# Voltege_inverter.net
KiCad netlist of a schematic drawn in Altium Designer
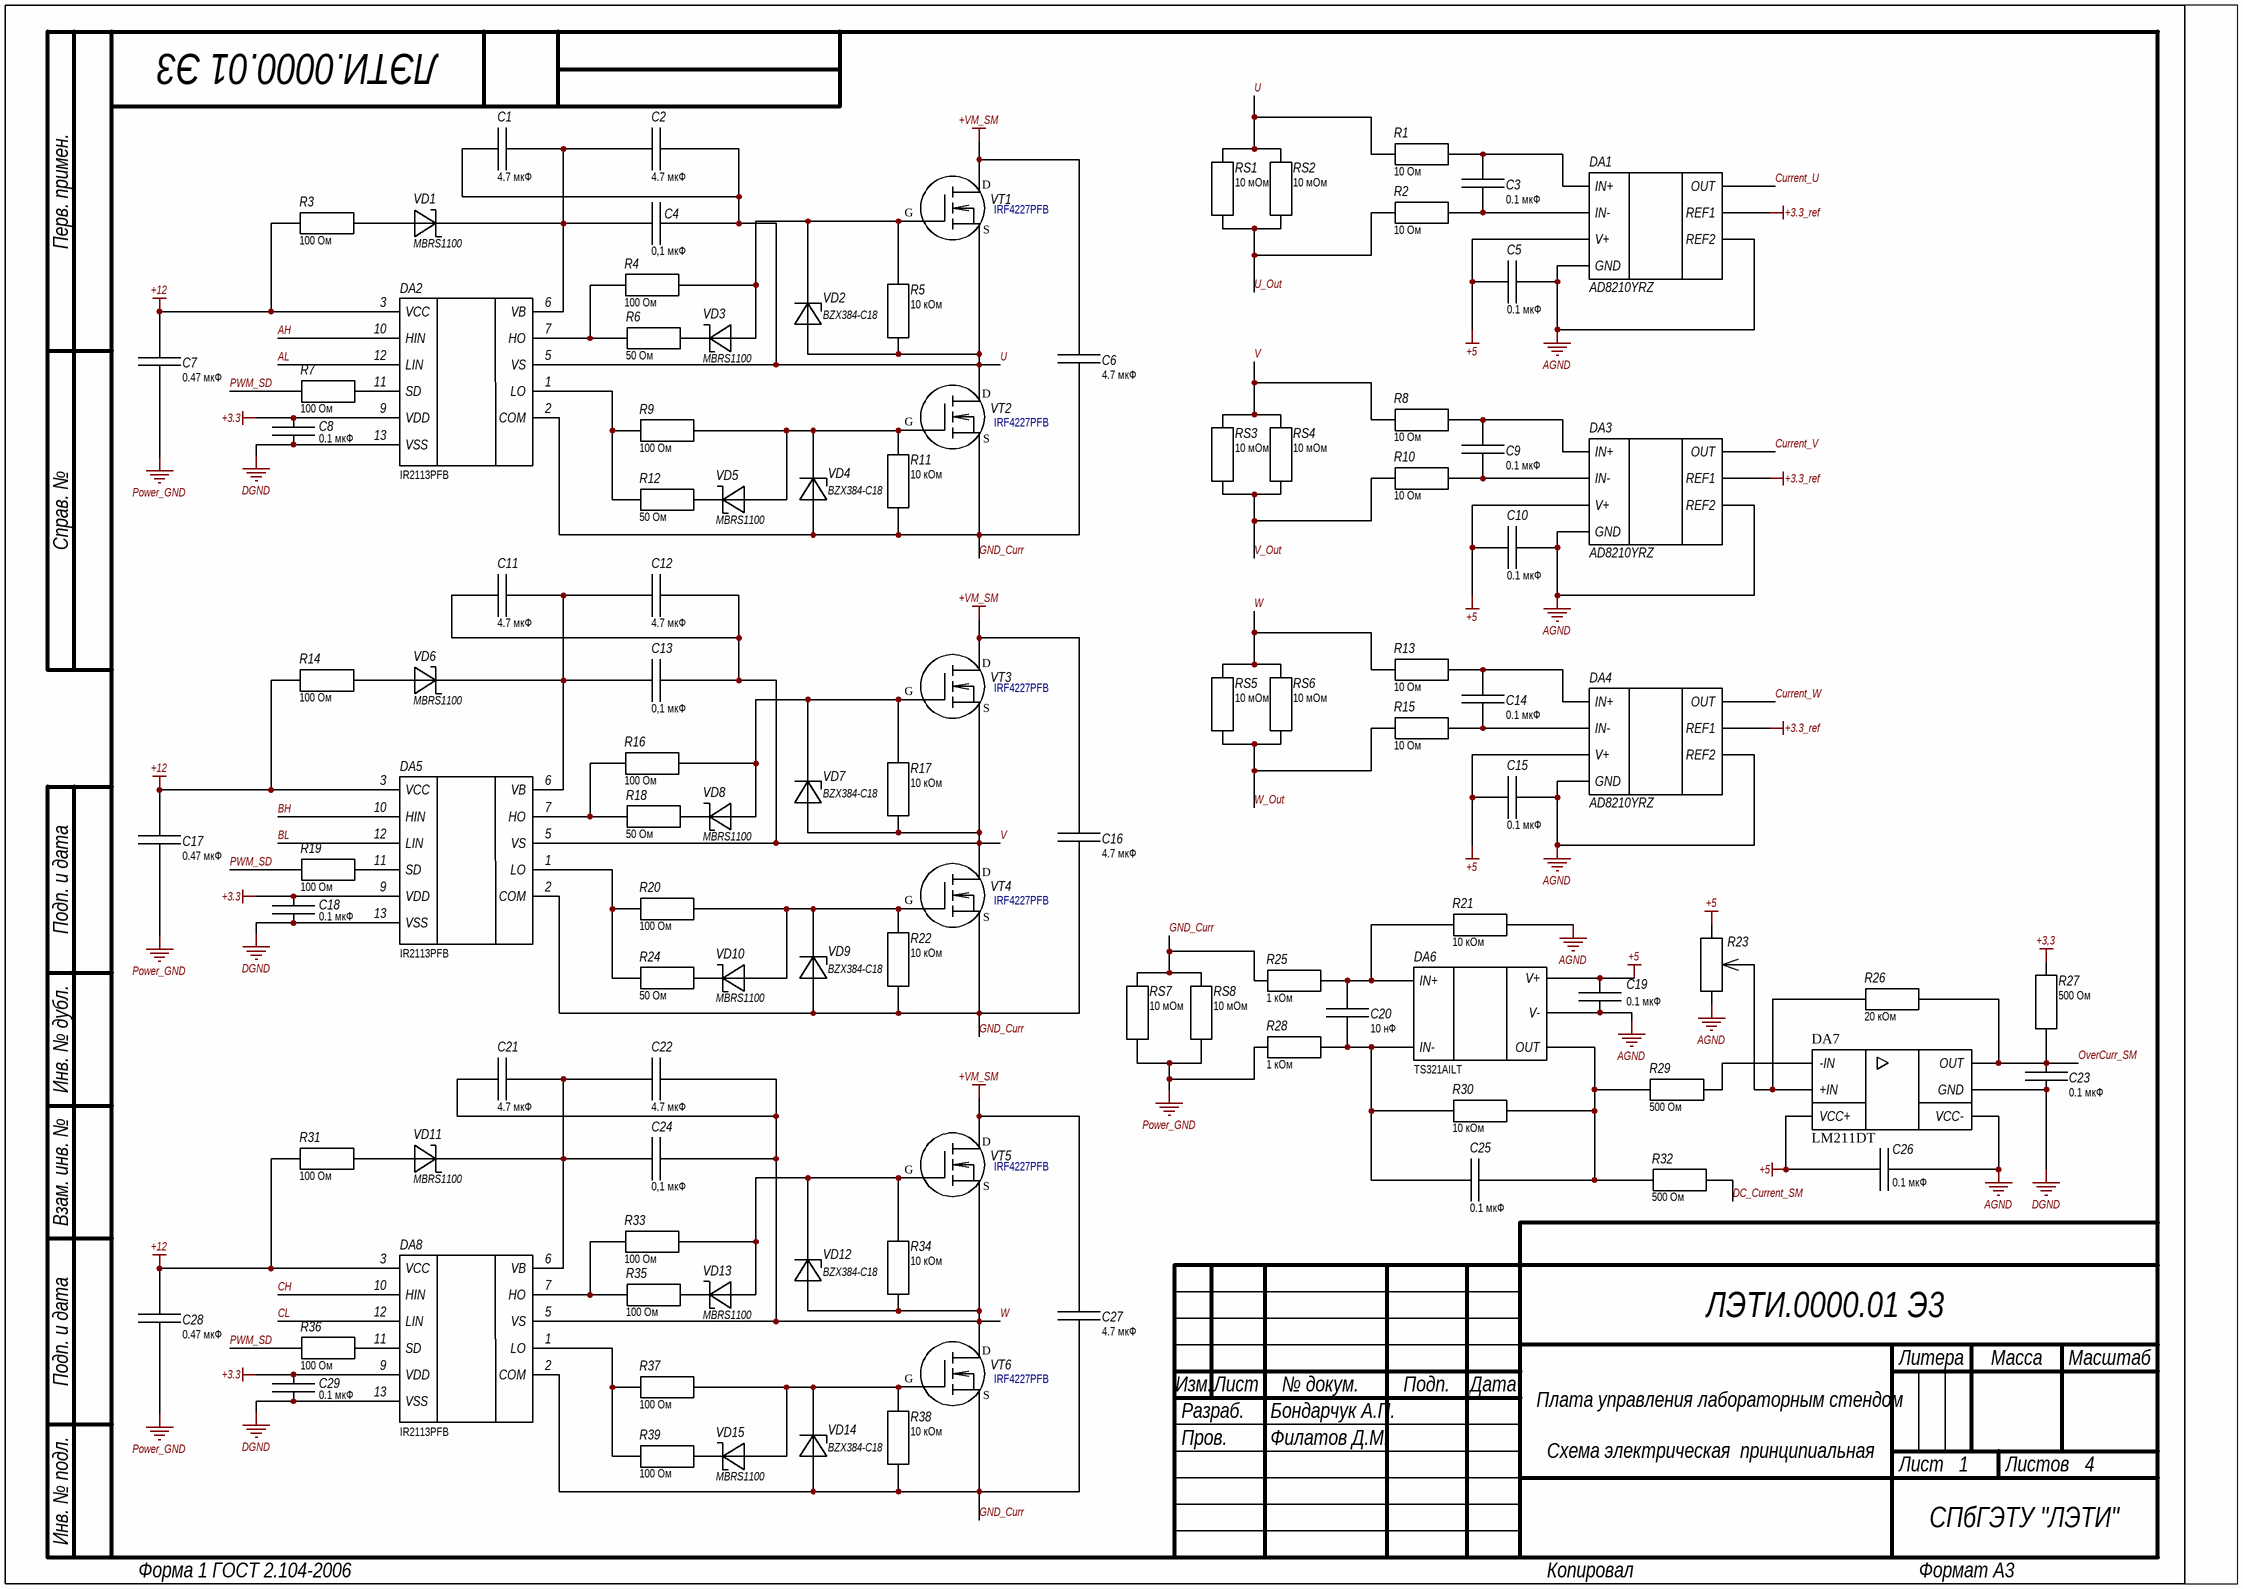
[diagram p0: Voltege_inverter.SchDoc]

(export (version "E")
  (design (tool "Eeschema 10.0.6"))
  (components
    (comp (ref "C1")
      (value "4.7 мкФ")
      (footprint "CC1210")
      (fields (field (name "VOLTAGE") "100В") (field (name "Comment") "Capacitor"))
      (libsource (lib "Main_components") (part "Capacitor"))
    )
    (comp (ref "C2")
      (value "4.7 мкФ")
      (footprint "CC1210")
      (fields (field (name "VOLTAGE") "100В") (field (name "Comment") "Capacitor"))
      (libsource (lib "Main_components") (part "Capacitor"))
    )
    (comp (ref "C3")
      (value "0.1 мкФ")
      (footprint "CC1206")
      (fields (field (name "VOLTAGE") "100В") (field (name "Comment") "Capacitor"))
      (libsource (lib "Main_components") (part "Capacitor"))
    )
    (comp (ref "C4")
      (value "0,1 мкФ")
      (footprint "CC0805")
      (fields (field (name "VOLTAGE") "100В") (field (name "Comment") "Capacitor"))
      (libsource (lib "Main_components") (part "Capacitor"))
    )
    (comp (ref "C5")
      (value "0.1 мкФ")
      (footprint "CC0603")
      (fields (field (name "VOLTAGE") "16В") (field (name "Comment") "Capacitor"))
      (libsource (lib "Main_components") (part "Capacitor"))
    )
    (comp (ref "C6")
      (value "4.7 мкФ")
      (footprint "CC1210")
      (fields (field (name "VOLTAGE") "100В") (field (name "Comment") "Capacitor"))
      (libsource (lib "Main_components") (part "Capacitor"))
    )
    (comp (ref "C7")
      (value "0.47 мкФ")
      (footprint "CC1206")
      (fields (field (name "VOLTAGE") "50В") (field (name "Comment") "Capacitor"))
      (libsource (lib "Main_components") (part "Capacitor"))
    )
    (comp (ref "C8")
      (value "0.1 мкФ")
      (footprint "CC0603")
      (fields (field (name "VOLTAGE") "16В") (field (name "Comment") "Capacitor"))
      (libsource (lib "Main_components") (part "Capacitor"))
    )
    (comp (ref "C9")
      (value "0.1 мкФ")
      (footprint "CC1206")
      (fields (field (name "VOLTAGE") "100В") (field (name "Comment") "Capacitor"))
      (libsource (lib "Main_components") (part "Capacitor"))
    )
    (comp (ref "C10")
      (value "0.1 мкФ")
      (footprint "CC0603")
      (fields (field (name "VOLTAGE") "16В") (field (name "Comment") "Capacitor"))
      (libsource (lib "Main_components") (part "Capacitor"))
    )
    (comp (ref "C11")
      (value "4.7 мкФ")
      (footprint "CC1210")
      (fields (field (name "VOLTAGE") "100В") (field (name "Comment") "Capacitor"))
      (libsource (lib "Main_components") (part "Capacitor"))
    )
    (comp (ref "C12")
      (value "4.7 мкФ")
      (footprint "CC1210")
      (fields (field (name "VOLTAGE") "100В") (field (name "Comment") "Capacitor"))
      (libsource (lib "Main_components") (part "Capacitor"))
    )
    (comp (ref "C13")
      (value "0,1 мкФ")
      (footprint "CC0805")
      (fields (field (name "VOLTAGE") "100В") (field (name "Comment") "Capacitor"))
      (libsource (lib "Main_components") (part "Capacitor"))
    )
    (comp (ref "C14")
      (value "0.1 мкФ")
      (footprint "CC1206")
      (fields (field (name "VOLTAGE") "100В") (field (name "Comment") "Capacitor"))
      (libsource (lib "Main_components") (part "Capacitor"))
    )
    (comp (ref "C15")
      (value "0.1 мкФ")
      (footprint "CC0603")
      (fields (field (name "VOLTAGE") "16В") (field (name "Comment") "Capacitor"))
      (libsource (lib "Main_components") (part "Capacitor"))
    )
    (comp (ref "C16")
      (value "4.7 мкФ")
      (footprint "CC1210")
      (fields (field (name "VOLTAGE") "100В") (field (name "Comment") "Capacitor"))
      (libsource (lib "Main_components") (part "Capacitor"))
    )
    (comp (ref "C17")
      (value "0.47 мкФ")
      (footprint "CC1206")
      (fields (field (name "VOLTAGE") "50В") (field (name "Comment") "Capacitor"))
      (libsource (lib "Main_components") (part "Capacitor"))
    )
    (comp (ref "C18")
      (value "0.1 мкФ")
      (footprint "CC0603")
      (fields (field (name "VOLTAGE") "16В") (field (name "Comment") "Capacitor"))
      (libsource (lib "Main_components") (part "Capacitor"))
    )
    (comp (ref "C19")
      (value "0.1 мкФ")
      (footprint "CC0603")
      (fields (field (name "VOLTAGE") "16В") (field (name "Comment") "Capacitor"))
      (libsource (lib "Main_components") (part "Capacitor"))
    )
    (comp (ref "C20")
      (value "10 нФ")
      (footprint "CC0805")
      (fields (field (name "VOLTAGE") "50В") (field (name "Comment") "Capacitor"))
      (libsource (lib "Main_components") (part "Capacitor"))
    )
    (comp (ref "C21")
      (value "4.7 мкФ")
      (footprint "CC1210")
      (fields (field (name "VOLTAGE") "100В") (field (name "Comment") "Capacitor"))
      (libsource (lib "Main_components") (part "Capacitor"))
    )
    (comp (ref "C22")
      (value "4.7 мкФ")
      (footprint "CC1210")
      (fields (field (name "VOLTAGE") "100В") (field (name "Comment") "Capacitor"))
      (libsource (lib "Main_components") (part "Capacitor"))
    )
    (comp (ref "C23")
      (value "0.1 мкФ")
      (footprint "CC0603")
      (fields (field (name "VOLTAGE") "16В") (field (name "Comment") "Capacitor"))
      (libsource (lib "Main_components") (part "Capacitor"))
    )
    (comp (ref "C24")
      (value "0,1 мкФ")
      (footprint "CC0805")
      (fields (field (name "VOLTAGE") "100В") (field (name "Comment") "Capacitor"))
      (libsource (lib "Main_components") (part "Capacitor"))
    )
    (comp (ref "C25")
      (value "0.1 мкФ")
      (footprint "CC1206")
      (fields (field (name "VOLTAGE") "100В") (field (name "Comment") "Capacitor"))
      (libsource (lib "Main_components") (part "Capacitor"))
    )
    (comp (ref "C26")
      (value "0.1 мкФ")
      (footprint "CC0603")
      (fields (field (name "VOLTAGE") "16В") (field (name "Comment") "Capacitor"))
      (libsource (lib "Main_components") (part "Capacitor"))
    )
    (comp (ref "C27")
      (value "4.7 мкФ")
      (footprint "CC1210")
      (fields (field (name "VOLTAGE") "100В") (field (name "Comment") "Capacitor"))
      (libsource (lib "Main_components") (part "Capacitor"))
    )
    (comp (ref "C28")
      (value "0.47 мкФ")
      (footprint "CC1206")
      (fields (field (name "VOLTAGE") "50В") (field (name "Comment") "Capacitor"))
      (libsource (lib "Main_components") (part "Capacitor"))
    )
    (comp (ref "C29")
      (value "0.1 мкФ")
      (footprint "CC0603")
      (fields (field (name "VOLTAGE") "16В") (field (name "Comment") "Capacitor"))
      (libsource (lib "Main_components") (part "Capacitor"))
    )
    (comp (ref "DA1") (value "AD8210YRZ") (footprint "SO8") (libsource (lib "Microcircuits") (part "AD8210")))
    (comp (ref "DA2")
      (value "IR2113PFB")
      (footprint "DIP14")
      (libsource (lib "Microcircuits") (part "IR2113PFB"))
    )
    (comp (ref "DA3") (value "AD8210YRZ") (footprint "SO8") (libsource (lib "Microcircuits") (part "AD8210")))
    (comp (ref "DA4") (value "AD8210YRZ") (footprint "SO8") (libsource (lib "Microcircuits") (part "AD8210")))
    (comp (ref "DA5")
      (value "IR2113PFB")
      (footprint "DIP14")
      (libsource (lib "Microcircuits") (part "IR2113PFB"))
    )
    (comp (ref "DA6")
      (value "TS321AILT")
      (footprint "SOT-23-5")
      (description "Одиночный операционный усилитель.")
      (libsource (lib "Microcircuits") (part "TS321AILT"))
    )
    (comp (ref "DA7")
      (value "LM211DT")
      (footprint "SO8")
      (description "Компаратор")
      (libsource (lib "Microcircuits") (part "LM211DT"))
    )
    (comp (ref "DA8")
      (value "IR2113PFB")
      (footprint "DIP14")
      (libsource (lib "Microcircuits") (part "IR2113PFB"))
    )
    (comp (ref "R1")
      (value "10 Ом")
      (footprint "RC1206")
      (fields (field (name "POWER") "250 мВт") (field (name "Comment") "Resistor"))
      (libsource (lib "Main_components") (part "Resistor"))
    )
    (comp (ref "R2")
      (value "10 Ом")
      (footprint "RC1206")
      (fields (field (name "POWER") "250 мВт") (field (name "Comment") "Resistor"))
      (libsource (lib "Main_components") (part "Resistor"))
    )
    (comp (ref "R3")
      (value "100 Ом")
      (footprint "RC2512")
      (fields (field (name "POWER") "1 Вт") (field (name "Comment") "Resistor"))
      (libsource (lib "Main_components") (part "Resistor"))
    )
    (comp (ref "R4")
      (value "100 Ом")
      (footprint "RC2512")
      (fields (field (name "POWER") "1 Вт") (field (name "Comment") "Resistor"))
      (libsource (lib "Main_components") (part "Resistor"))
    )
    (comp (ref "R5")
      (value "10 кОм")
      (footprint "RC0805")
      (fields (field (name "POWER") "125 мВт") (field (name "Comment") "Resistor"))
      (libsource (lib "Main_components") (part "Resistor"))
    )
    (comp (ref "R6")
      (value "50 Ом")
      (footprint "RC2512")
      (fields (field (name "POWER") "1 Вт") (field (name "Comment") "Resistor"))
      (libsource (lib "Main_components") (part "Resistor"))
    )
    (comp (ref "R7")
      (value "100 Ом")
      (footprint "RC0603")
      (fields (field (name "POWER") "100 мВт") (field (name "Comment") "Resistor"))
      (libsource (lib "Main_components") (part "Resistor"))
    )
    (comp (ref "R8")
      (value "10 Ом")
      (footprint "RC1206")
      (fields (field (name "POWER") "250 мВт") (field (name "Comment") "Resistor"))
      (libsource (lib "Main_components") (part "Resistor"))
    )
    (comp (ref "R9")
      (value "100 Ом")
      (footprint "RC2512")
      (fields (field (name "POWER") "1 Вт") (field (name "Comment") "Resistor"))
      (libsource (lib "Main_components") (part "Resistor"))
    )
    (comp (ref "R10")
      (value "10 Ом")
      (footprint "RC1206")
      (fields (field (name "POWER") "250 мВт") (field (name "Comment") "Resistor"))
      (libsource (lib "Main_components") (part "Resistor"))
    )
    (comp (ref "R11")
      (value "10 кОм")
      (footprint "RC0805")
      (fields (field (name "POWER") "125 мВт") (field (name "Comment") "Resistor"))
      (libsource (lib "Main_components") (part "Resistor"))
    )
    (comp (ref "R12")
      (value "50 Ом")
      (footprint "RC2512")
      (fields (field (name "POWER") "1 Вт") (field (name "Comment") "Resistor"))
      (libsource (lib "Main_components") (part "Resistor"))
    )
    (comp (ref "R13")
      (value "10 Ом")
      (footprint "RC1206")
      (fields (field (name "POWER") "250 мВт") (field (name "Comment") "Resistor"))
      (libsource (lib "Main_components") (part "Resistor"))
    )
    (comp (ref "R14")
      (value "100 Ом")
      (footprint "RC2512")
      (fields (field (name "POWER") "1 Вт") (field (name "Comment") "Resistor"))
      (libsource (lib "Main_components") (part "Resistor"))
    )
    (comp (ref "R15")
      (value "10 Ом")
      (footprint "RC1206")
      (fields (field (name "POWER") "250 мВт") (field (name "Comment") "Resistor"))
      (libsource (lib "Main_components") (part "Resistor"))
    )
    (comp (ref "R16")
      (value "100 Ом")
      (footprint "RC2512")
      (fields (field (name "POWER") "1 Вт") (field (name "Comment") "Resistor"))
      (libsource (lib "Main_components") (part "Resistor"))
    )
    (comp (ref "R17")
      (value "10 кОм")
      (footprint "RC0805")
      (fields (field (name "POWER") "125 мВт") (field (name "Comment") "Resistor"))
      (libsource (lib "Main_components") (part "Resistor"))
    )
    (comp (ref "R18")
      (value "50 Ом")
      (footprint "RC2512")
      (fields (field (name "POWER") "1 Вт") (field (name "Comment") "Resistor"))
      (libsource (lib "Main_components") (part "Resistor"))
    )
    (comp (ref "R19")
      (value "100 Ом")
      (footprint "RC0603")
      (fields (field (name "POWER") "100 мВт") (field (name "Comment") "Resistor"))
      (libsource (lib "Main_components") (part "Resistor"))
    )
    (comp (ref "R20")
      (value "100 Ом")
      (footprint "RC2512")
      (fields (field (name "POWER") "1 Вт") (field (name "Comment") "Resistor"))
      (libsource (lib "Main_components") (part "Resistor"))
    )
    (comp (ref "R21")
      (value "10 кОм")
      (footprint "RC0805")
      (fields (field (name "POWER") "125 мВт") (field (name "Comment") "Resistor"))
      (libsource (lib "Main_components") (part "Resistor"))
    )
    (comp (ref "R22")
      (value "10 кОм")
      (footprint "RC0805")
      (fields (field (name "POWER") "125 мВт") (field (name "Comment") "Resistor"))
      (libsource (lib "Main_components") (part "Resistor"))
    )
    (comp (ref "R23") (value "pot") (footprint "3296W") (libsource (lib "Main_components") (part "pot")))
    (comp (ref "R24")
      (value "50 Ом")
      (footprint "RC2512")
      (fields (field (name "POWER") "1 Вт") (field (name "Comment") "Resistor"))
      (libsource (lib "Main_components") (part "Resistor"))
    )
    (comp (ref "R25")
      (value "1 кОм")
      (footprint "RC0805")
      (fields (field (name "POWER") "125 мВт") (field (name "Comment") "Resistor"))
      (libsource (lib "Main_components") (part "Resistor"))
    )
    (comp (ref "R26")
      (value "20 кОм")
      (footprint "RC0805")
      (fields (field (name "POWER") "125 мВт") (field (name "Comment") "Resistor"))
      (libsource (lib "Main_components") (part "Resistor"))
    )
    (comp (ref "R27")
      (value "500 Ом")
      (footprint "RC0805")
      (fields (field (name "POWER") "125 мВт") (field (name "Comment") "Resistor"))
      (libsource (lib "Main_components") (part "Resistor"))
    )
    (comp (ref "R28")
      (value "1 кОм")
      (footprint "RC0805")
      (fields (field (name "POWER") "125 мВт") (field (name "Comment") "Resistor"))
      (libsource (lib "Main_components") (part "Resistor"))
    )
    (comp (ref "R29")
      (value "500 Ом")
      (footprint "RC0805")
      (fields (field (name "POWER") "125 мВт") (field (name "Comment") "Resistor"))
      (libsource (lib "Main_components") (part "Resistor"))
    )
    (comp (ref "R30")
      (value "10 кОм")
      (footprint "RC0805")
      (fields (field (name "POWER") "125 мВт") (field (name "Comment") "Resistor"))
      (libsource (lib "Main_components") (part "Resistor"))
    )
    (comp (ref "R31")
      (value "100 Ом")
      (footprint "RC2512")
      (fields (field (name "POWER") "1 Вт") (field (name "Comment") "Resistor"))
      (libsource (lib "Main_components") (part "Resistor"))
    )
    (comp (ref "R32")
      (value "500 Ом")
      (footprint "RC0805")
      (fields (field (name "POWER") "125 мВт") (field (name "Comment") "Resistor"))
      (libsource (lib "Main_components") (part "Resistor"))
    )
    (comp (ref "R33")
      (value "100 Ом")
      (footprint "RC2512")
      (fields (field (name "POWER") "1 Вт") (field (name "Comment") "Resistor"))
      (libsource (lib "Main_components") (part "Resistor"))
    )
    (comp (ref "R34")
      (value "10 кОм")
      (footprint "RC0805")
      (fields (field (name "POWER") "125 мВт") (field (name "Comment") "Resistor"))
      (libsource (lib "Main_components") (part "Resistor"))
    )
    (comp (ref "R35")
      (value "100 Ом")
      (footprint "RC2512")
      (fields (field (name "POWER") "1 Вт") (field (name "Comment") "Resistor"))
      (libsource (lib "Main_components") (part "Resistor"))
    )
    (comp (ref "R36")
      (value "100 Ом")
      (footprint "RC0603")
      (fields (field (name "POWER") "100 мВт") (field (name "Comment") "Resistor"))
      (libsource (lib "Main_components") (part "Resistor"))
    )
    (comp (ref "R37")
      (value "100 Ом")
      (footprint "RC2512")
      (fields (field (name "POWER") "1 Вт") (field (name "Comment") "Resistor"))
      (libsource (lib "Main_components") (part "Resistor"))
    )
    (comp (ref "R38")
      (value "10 кОм")
      (footprint "RC0805")
      (fields (field (name "POWER") "125 мВт") (field (name "Comment") "Resistor"))
      (libsource (lib "Main_components") (part "Resistor"))
    )
    (comp (ref "R39")
      (value "100 Ом")
      (footprint "RC2512")
      (fields (field (name "POWER") "1 Вт") (field (name "Comment") "Resistor"))
      (libsource (lib "Main_components") (part "Resistor"))
    )
    (comp (ref "RS1")
      (value "10 мОм")
      (footprint "RC2816")
      (fields (field (name "POWER") "2 Вт") (field (name "Comment") "Resistor"))
      (libsource (lib "Main_components") (part "Resistor"))
    )
    (comp (ref "RS2")
      (value "10 мОм")
      (footprint "RC2816")
      (fields (field (name "POWER") "2 Вт") (field (name "Comment") "Resistor"))
      (libsource (lib "Main_components") (part "Resistor"))
    )
    (comp (ref "RS3")
      (value "10 мОм")
      (footprint "RC2816")
      (fields (field (name "POWER") "2 Вт") (field (name "Comment") "Resistor"))
      (libsource (lib "Main_components") (part "Resistor"))
    )
    (comp (ref "RS4")
      (value "10 мОм")
      (footprint "RC2816")
      (fields (field (name "POWER") "2 Вт") (field (name "Comment") "Resistor"))
      (libsource (lib "Main_components") (part "Resistor"))
    )
    (comp (ref "RS5")
      (value "10 мОм")
      (footprint "RC2816")
      (fields (field (name "POWER") "2 Вт") (field (name "Comment") "Resistor"))
      (libsource (lib "Main_components") (part "Resistor"))
    )
    (comp (ref "RS6")
      (value "10 мОм")
      (footprint "RC2816")
      (fields (field (name "POWER") "2 Вт") (field (name "Comment") "Resistor"))
      (libsource (lib "Main_components") (part "Resistor"))
    )
    (comp (ref "RS7")
      (value "10 мОм")
      (footprint "RC2816")
      (fields (field (name "POWER") "2 Вт") (field (name "Comment") "Resistor"))
      (libsource (lib "Main_components") (part "Resistor"))
    )
    (comp (ref "RS8")
      (value "10 мОм")
      (footprint "RC2816")
      (fields (field (name "POWER") "2 Вт") (field (name "Comment") "Resistor"))
      (libsource (lib "Main_components") (part "Resistor"))
    )
    (comp (ref "VD1")
      (value "MBRS1100")
      (footprint "DO-214AA")
      (libsource (lib "Main_components") (part "Shotki"))
    )
    (comp (ref "VD2")
      (value "BZX384-C18")
      (footprint "SOD323")
      (libsource (lib "InvertorSchLib") (part "Zener diode"))
    )
    (comp (ref "VD3")
      (value "MBRS1100")
      (footprint "DO-214AA")
      (libsource (lib "Main_components") (part "Shotki"))
    )
    (comp (ref "VD4")
      (value "BZX384-C18")
      (footprint "SOD323")
      (libsource (lib "InvertorSchLib") (part "Zener diode"))
    )
    (comp (ref "VD5")
      (value "MBRS1100")
      (footprint "DO-214AA")
      (libsource (lib "Main_components") (part "Shotki"))
    )
    (comp (ref "VD6")
      (value "MBRS1100")
      (footprint "DO-214AA")
      (libsource (lib "Main_components") (part "Shotki"))
    )
    (comp (ref "VD7")
      (value "BZX384-C18")
      (footprint "SOD323")
      (libsource (lib "InvertorSchLib") (part "Zener diode"))
    )
    (comp (ref "VD8")
      (value "MBRS1100")
      (footprint "DO-214AA")
      (libsource (lib "Main_components") (part "Shotki"))
    )
    (comp (ref "VD9")
      (value "BZX384-C18")
      (footprint "SOD323")
      (libsource (lib "InvertorSchLib") (part "Zener diode"))
    )
    (comp (ref "VD10")
      (value "MBRS1100")
      (footprint "DO-214AA")
      (libsource (lib "Main_components") (part "Shotki"))
    )
    (comp (ref "VD11")
      (value "MBRS1100")
      (footprint "DO-214AA")
      (libsource (lib "Main_components") (part "Shotki"))
    )
    (comp (ref "VD12")
      (value "BZX384-C18")
      (footprint "SOD323")
      (libsource (lib "InvertorSchLib") (part "Zener diode"))
    )
    (comp (ref "VD13")
      (value "MBRS1100")
      (footprint "DO-214AA")
      (libsource (lib "Main_components") (part "Shotki"))
    )
    (comp (ref "VD14")
      (value "BZX384-C18")
      (footprint "SOD323")
      (libsource (lib "InvertorSchLib") (part "Zener diode"))
    )
    (comp (ref "VD15")
      (value "MBRS1100")
      (footprint "DO-214AA")
      (libsource (lib "Main_components") (part "Shotki"))
    )
    (comp (ref "VT1")
      (value "IRF4227PFB")
      (footprint "TO247-1")
      (libsource (lib "Main_components") (part "N-MOSFET"))
    )
    (comp (ref "VT2")
      (value "IRF4227PFB")
      (footprint "TO247-1")
      (libsource (lib "Main_components") (part "N-MOSFET"))
    )
    (comp (ref "VT3")
      (value "IRF4227PFB")
      (footprint "TO247-1")
      (libsource (lib "Main_components") (part "N-MOSFET"))
    )
    (comp (ref "VT4")
      (value "IRF4227PFB")
      (footprint "TO247-1")
      (libsource (lib "Main_components") (part "N-MOSFET"))
    )
    (comp (ref "VT5")
      (value "IRF4227PFB")
      (footprint "TO247-1")
      (libsource (lib "Main_components") (part "N-MOSFET"))
    )
    (comp (ref "VT6")
      (value "IRF4227PFB")
      (footprint "TO247-1")
      (libsource (lib "Main_components") (part "N-MOSFET"))
    )
  )
  (nets
    (net (code "1") (name "+3,3") (class "Default")
      (node (ref "R27") (pin "2") (pinfunction "2_2") (pintype "passive"))
    )
    (net (code "2") (name "+3.3") (class "Default")
      (node (ref "C18") (pin "2") (pinfunction "2_2") (pintype "passive"))
      (node (ref "C29") (pin "2") (pinfunction "2_2") (pintype "passive"))
      (node (ref "C8") (pin "2") (pinfunction "2_2") (pintype "passive"))
      (node (ref "DA2") (pin "9") (pinfunction "VDD_9") (pintype "passive"))
      (node (ref "DA5") (pin "9") (pinfunction "VDD_9") (pintype "passive"))
      (node (ref "DA8") (pin "9") (pinfunction "VDD_9") (pintype "passive"))
    )
    (net (code "3") (name "+3.3_ref") (class "Default")
      (node (ref "DA1") (pin "7") (pinfunction "REF1_7") (pintype "passive"))
      (node (ref "DA3") (pin "7") (pinfunction "REF1_7") (pintype "passive"))
      (node (ref "DA4") (pin "7") (pinfunction "REF1_7") (pintype "passive"))
    )
    (net (code "4") (name "+5") (class "Default")
      (node (ref "C10") (pin "2") (pinfunction "2_2") (pintype "passive"))
      (node (ref "C15") (pin "2") (pinfunction "2_2") (pintype "passive"))
      (node (ref "C19") (pin "1") (pinfunction "1_1") (pintype "passive"))
      (node (ref "C26") (pin "1") (pinfunction "1_1") (pintype "passive"))
      (node (ref "C5") (pin "2") (pinfunction "2_2") (pintype "passive"))
      (node (ref "DA1") (pin "6") (pinfunction "V+_6") (pintype "passive"))
      (node (ref "DA3") (pin "6") (pinfunction "V+_6") (pintype "passive"))
      (node (ref "DA4") (pin "6") (pinfunction "V+_6") (pintype "passive"))
      (node (ref "DA6") (pin "5") (pinfunction "V+_5") (pintype "passive"))
      (node (ref "DA7") (pin "8") (pinfunction "VCC+_8") (pintype "passive"))
      (node (ref "R23") (pin "1") (pinfunction "1_1") (pintype "passive"))
    )
    (net (code "5") (name "+12") (class "Default")
      (node (ref "C17") (pin "2") (pinfunction "2_2") (pintype "passive"))
      (node (ref "C28") (pin "2") (pinfunction "2_2") (pintype "passive"))
      (node (ref "C7") (pin "2") (pinfunction "2_2") (pintype "passive"))
      (node (ref "DA2") (pin "3") (pinfunction "VCC_3") (pintype "passive"))
      (node (ref "DA5") (pin "3") (pinfunction "VCC_3") (pintype "passive"))
      (node (ref "DA8") (pin "3") (pinfunction "VCC_3") (pintype "passive"))
      (node (ref "R14") (pin "2") (pinfunction "2_2") (pintype "passive"))
      (node (ref "R3") (pin "2") (pinfunction "2_2") (pintype "passive"))
      (node (ref "R31") (pin "2") (pinfunction "2_2") (pintype "passive"))
    )
    (net (code "6") (name "+VM_SM") (class "Default")
      (node (ref "C16") (pin "2") (pinfunction "2_2") (pintype "passive"))
      (node (ref "C27") (pin "2") (pinfunction "2_2") (pintype "passive"))
      (node (ref "C6") (pin "2") (pinfunction "2_2") (pintype "passive"))
      (node (ref "VT1") (pin "D") (pinfunction "D_D") (pintype "passive"))
      (node (ref "VT3") (pin "D") (pinfunction "D_D") (pintype "passive"))
      (node (ref "VT5") (pin "D") (pinfunction "D_D") (pintype "passive"))
    )
    (net (code "7") (name "/AH") (class "Default")
      (node (ref "DA2") (pin "10") (pinfunction "HIN_10") (pintype "passive"))
    )
    (net (code "8") (name "/AL") (class "Default")
      (node (ref "DA2") (pin "12") (pinfunction "LIN_12") (pintype "passive"))
    )
    (net (code "9") (name "/BH") (class "Default")
      (node (ref "DA5") (pin "10") (pinfunction "HIN_10") (pintype "passive"))
    )
    (net (code "10") (name "/BL") (class "Default")
      (node (ref "DA5") (pin "12") (pinfunction "LIN_12") (pintype "passive"))
    )
    (net (code "11") (name "/CH") (class "Default")
      (node (ref "DA8") (pin "10") (pinfunction "HIN_10") (pintype "passive"))
    )
    (net (code "12") (name "/CL") (class "Default")
      (node (ref "DA8") (pin "12") (pinfunction "LIN_12") (pintype "passive"))
    )
    (net (code "13") (name "/Current_U") (class "Default")
      (node (ref "DA1") (pin "5") (pinfunction "OUT_5") (pintype "passive"))
    )
    (net (code "14") (name "/Current_V") (class "Default")
      (node (ref "DA3") (pin "5") (pinfunction "OUT_5") (pintype "passive"))
    )
    (net (code "15") (name "/Current_W") (class "Default")
      (node (ref "DA4") (pin "5") (pinfunction "OUT_5") (pintype "passive"))
    )
    (net (code "16") (name "/DC_Current_SM") (class "Default")
      (node (ref "R32") (pin "2") (pinfunction "2_2") (pintype "passive"))
    )
    (net (code "17") (name "/GND_Curr") (class "Default")
      (node (ref "C16") (pin "1") (pinfunction "1_1") (pintype "passive"))
      (node (ref "C27") (pin "1") (pinfunction "1_1") (pintype "passive"))
      (node (ref "C6") (pin "1") (pinfunction "1_1") (pintype "passive"))
      (node (ref "DA2") (pin "2") (pinfunction "COM_2") (pintype "passive"))
      (node (ref "DA5") (pin "2") (pinfunction "COM_2") (pintype "passive"))
      (node (ref "DA8") (pin "2") (pinfunction "COM_2") (pintype "passive"))
      (node (ref "R11") (pin "2") (pinfunction "2_2") (pintype "passive"))
      (node (ref "R22") (pin "2") (pinfunction "2_2") (pintype "passive"))
      (node (ref "R25") (pin "1") (pinfunction "1_1") (pintype "passive"))
      (node (ref "R38") (pin "2") (pinfunction "2_2") (pintype "passive"))
      (node (ref "RS7") (pin "1") (pinfunction "1_1") (pintype "passive"))
      (node (ref "RS8") (pin "1") (pinfunction "1_1") (pintype "passive"))
      (node (ref "VD14") (pin "A") (pinfunction "A_A") (pintype "passive"))
      (node (ref "VD4") (pin "A") (pinfunction "A_A") (pintype "passive"))
      (node (ref "VD9") (pin "A") (pinfunction "A_A") (pintype "passive"))
      (node (ref "VT2") (pin "S") (pinfunction "S_S") (pintype "passive"))
      (node (ref "VT4") (pin "S") (pinfunction "S_S") (pintype "passive"))
      (node (ref "VT6") (pin "S") (pinfunction "S_S") (pintype "passive"))
    )
    (net (code "18") (name "/OverCurr_SM") (class "Default")
      (node (ref "C23") (pin "2") (pinfunction "2_2") (pintype "passive"))
      (node (ref "DA7") (pin "7") (pinfunction "OUT_7") (pintype "passive"))
      (node (ref "R26") (pin "2") (pinfunction "2_2") (pintype "passive"))
      (node (ref "R27") (pin "1") (pinfunction "1_1") (pintype "passive"))
    )
    (net (code "19") (name "/PWM_SD") (class "Default")
      (node (ref "R19") (pin "2") (pinfunction "2_2") (pintype "passive"))
      (node (ref "R36") (pin "2") (pinfunction "2_2") (pintype "passive"))
      (node (ref "R7") (pin "2") (pinfunction "2_2") (pintype "passive"))
    )
    (net (code "20") (name "/U") (class "Default")
      (node (ref "C1") (pin "2") (pinfunction "2_2") (pintype "passive"))
      (node (ref "C2") (pin "1") (pinfunction "1_1") (pintype "passive"))
      (node (ref "C4") (pin "1") (pinfunction "1_1") (pintype "passive"))
      (node (ref "DA2") (pin "5") (pinfunction "VS_5") (pintype "passive"))
      (node (ref "R1") (pin "2") (pinfunction "2_2") (pintype "passive"))
      (node (ref "R5") (pin "2") (pinfunction "2_2") (pintype "passive"))
      (node (ref "RS1") (pin "1") (pinfunction "1_1") (pintype "passive"))
      (node (ref "RS2") (pin "1") (pinfunction "1_1") (pintype "passive"))
      (node (ref "VD2") (pin "A") (pinfunction "A_A") (pintype "passive"))
      (node (ref "VT1") (pin "S") (pinfunction "S_S") (pintype "passive"))
      (node (ref "VT2") (pin "D") (pinfunction "D_D") (pintype "passive"))
    )
    (net (code "21") (name "/U_Out") (class "Default")
      (node (ref "R2") (pin "2") (pinfunction "2_2") (pintype "passive"))
      (node (ref "RS1") (pin "2") (pinfunction "2_2") (pintype "passive"))
      (node (ref "RS2") (pin "2") (pinfunction "2_2") (pintype "passive"))
    )
    (net (code "22") (name "/V") (class "Default")
      (node (ref "C11") (pin "2") (pinfunction "2_2") (pintype "passive"))
      (node (ref "C12") (pin "1") (pinfunction "1_1") (pintype "passive"))
      (node (ref "C13") (pin "1") (pinfunction "1_1") (pintype "passive"))
      (node (ref "DA5") (pin "5") (pinfunction "VS_5") (pintype "passive"))
      (node (ref "R17") (pin "2") (pinfunction "2_2") (pintype "passive"))
      (node (ref "R8") (pin "2") (pinfunction "2_2") (pintype "passive"))
      (node (ref "RS3") (pin "1") (pinfunction "1_1") (pintype "passive"))
      (node (ref "RS4") (pin "1") (pinfunction "1_1") (pintype "passive"))
      (node (ref "VD7") (pin "A") (pinfunction "A_A") (pintype "passive"))
      (node (ref "VT3") (pin "S") (pinfunction "S_S") (pintype "passive"))
      (node (ref "VT4") (pin "D") (pinfunction "D_D") (pintype "passive"))
    )
    (net (code "23") (name "/V_Out") (class "Default")
      (node (ref "R10") (pin "2") (pinfunction "2_2") (pintype "passive"))
      (node (ref "RS3") (pin "2") (pinfunction "2_2") (pintype "passive"))
      (node (ref "RS4") (pin "2") (pinfunction "2_2") (pintype "passive"))
    )
    (net (code "24") (name "/W") (class "Default")
      (node (ref "C21") (pin "2") (pinfunction "2_2") (pintype "passive"))
      (node (ref "C22") (pin "1") (pinfunction "1_1") (pintype "passive"))
      (node (ref "C24") (pin "1") (pinfunction "1_1") (pintype "passive"))
      (node (ref "DA8") (pin "5") (pinfunction "VS_5") (pintype "passive"))
      (node (ref "R13") (pin "2") (pinfunction "2_2") (pintype "passive"))
      (node (ref "R34") (pin "2") (pinfunction "2_2") (pintype "passive"))
      (node (ref "RS5") (pin "1") (pinfunction "1_1") (pintype "passive"))
      (node (ref "RS6") (pin "1") (pinfunction "1_1") (pintype "passive"))
      (node (ref "VD12") (pin "A") (pinfunction "A_A") (pintype "passive"))
      (node (ref "VT5") (pin "S") (pinfunction "S_S") (pintype "passive"))
      (node (ref "VT6") (pin "D") (pinfunction "D_D") (pintype "passive"))
    )
    (net (code "25") (name "/W_Out") (class "Default")
      (node (ref "R15") (pin "2") (pinfunction "2_2") (pintype "passive"))
      (node (ref "RS5") (pin "2") (pinfunction "2_2") (pintype "passive"))
      (node (ref "RS6") (pin "2") (pinfunction "2_2") (pintype "passive"))
    )
    (net (code "26") (name "AGND") (class "Default")
      (node (ref "C10") (pin "1") (pinfunction "1_1") (pintype "passive"))
      (node (ref "C15") (pin "1") (pinfunction "1_1") (pintype "passive"))
      (node (ref "C19") (pin "2") (pinfunction "2_2") (pintype "passive"))
      (node (ref "C26") (pin "2") (pinfunction "2_2") (pintype "passive"))
      (node (ref "C5") (pin "1") (pinfunction "1_1") (pintype "passive"))
      (node (ref "DA1") (pin "2") (pinfunction "GND_2") (pintype "passive"))
      (node (ref "DA1") (pin "3") (pinfunction "REF2_3") (pintype "passive"))
      (node (ref "DA3") (pin "2") (pinfunction "GND_2") (pintype "passive"))
      (node (ref "DA3") (pin "3") (pinfunction "REF2_3") (pintype "passive"))
      (node (ref "DA4") (pin "2") (pinfunction "GND_2") (pintype "passive"))
      (node (ref "DA4") (pin "3") (pinfunction "REF2_3") (pintype "passive"))
      (node (ref "DA6") (pin "2") (pinfunction "V-_2") (pintype "passive"))
      (node (ref "DA7") (pin "4") (pinfunction "VCC-_4") (pintype "passive"))
      (node (ref "R21") (pin "2") (pinfunction "2_2") (pintype "passive"))
      (node (ref "R23") (pin "3") (pinfunction "3_3") (pintype "passive"))
    )
    (net (code "27") (name "DGND") (class "Default")
      (node (ref "C18") (pin "1") (pinfunction "1_1") (pintype "passive"))
      (node (ref "C23") (pin "1") (pinfunction "1_1") (pintype "passive"))
      (node (ref "C29") (pin "1") (pinfunction "1_1") (pintype "passive"))
      (node (ref "C8") (pin "1") (pinfunction "1_1") (pintype "passive"))
      (node (ref "DA2") (pin "13") (pinfunction "VSS_13") (pintype "passive"))
      (node (ref "DA5") (pin "13") (pinfunction "VSS_13") (pintype "passive"))
      (node (ref "DA7") (pin "1") (pinfunction "GND_1") (pintype "passive"))
      (node (ref "DA8") (pin "13") (pinfunction "VSS_13") (pintype "passive"))
    )
    (net (code "28") (name "Net-(DA1-IN+)") (class "Default")
      (node (ref "C3") (pin "1") (pinfunction "1_1") (pintype "passive"))
      (node (ref "DA1") (pin "8") (pinfunction "IN+_8") (pintype "passive"))
      (node (ref "R1") (pin "1") (pinfunction "1_1") (pintype "passive"))
    )
    (net (code "29") (name "Net-(DA1-IN-)") (class "Default")
      (node (ref "C3") (pin "2") (pinfunction "2_2") (pintype "passive"))
      (node (ref "DA1") (pin "1") (pinfunction "IN-_1") (pintype "passive"))
      (node (ref "R2") (pin "1") (pinfunction "1_1") (pintype "passive"))
    )
    (net (code "30") (name "Net-(DA2-HO)") (class "Default")
      (node (ref "DA2") (pin "7") (pinfunction "HO_7") (pintype "passive"))
      (node (ref "R4") (pin "2") (pinfunction "2_2") (pintype "passive"))
      (node (ref "R6") (pin "2") (pinfunction "2_2") (pintype "passive"))
    )
    (net (code "31") (name "Net-(DA2-LO)") (class "Default")
      (node (ref "DA2") (pin "1") (pinfunction "LO_1") (pintype "passive"))
      (node (ref "R12") (pin "2") (pinfunction "2_2") (pintype "passive"))
      (node (ref "R9") (pin "2") (pinfunction "2_2") (pintype "passive"))
    )
    (net (code "32") (name "Net-(DA2-SD)") (class "Default")
      (node (ref "DA2") (pin "11") (pinfunction "SD_11") (pintype "passive"))
      (node (ref "R7") (pin "1") (pinfunction "1_1") (pintype "passive"))
    )
    (net (code "33") (name "Net-(DA2-VB)") (class "Default")
      (node (ref "C1") (pin "1") (pinfunction "1_1") (pintype "passive"))
      (node (ref "C2") (pin "2") (pinfunction "2_2") (pintype "passive"))
      (node (ref "C4") (pin "2") (pinfunction "2_2") (pintype "passive"))
      (node (ref "DA2") (pin "6") (pinfunction "VB_6") (pintype "passive"))
      (node (ref "VD1") (pin "C") (pinfunction "C_C") (pintype "passive"))
    )
    (net (code "34") (name "Net-(DA3-IN+)") (class "Default")
      (node (ref "C9") (pin "1") (pinfunction "1_1") (pintype "passive"))
      (node (ref "DA3") (pin "8") (pinfunction "IN+_8") (pintype "passive"))
      (node (ref "R8") (pin "1") (pinfunction "1_1") (pintype "passive"))
    )
    (net (code "35") (name "Net-(DA3-IN-)") (class "Default")
      (node (ref "C9") (pin "2") (pinfunction "2_2") (pintype "passive"))
      (node (ref "DA3") (pin "1") (pinfunction "IN-_1") (pintype "passive"))
      (node (ref "R10") (pin "1") (pinfunction "1_1") (pintype "passive"))
    )
    (net (code "36") (name "Net-(DA4-IN+)") (class "Default")
      (node (ref "C14") (pin "1") (pinfunction "1_1") (pintype "passive"))
      (node (ref "DA4") (pin "8") (pinfunction "IN+_8") (pintype "passive"))
      (node (ref "R13") (pin "1") (pinfunction "1_1") (pintype "passive"))
    )
    (net (code "37") (name "Net-(DA4-IN-)") (class "Default")
      (node (ref "C14") (pin "2") (pinfunction "2_2") (pintype "passive"))
      (node (ref "DA4") (pin "1") (pinfunction "IN-_1") (pintype "passive"))
      (node (ref "R15") (pin "1") (pinfunction "1_1") (pintype "passive"))
    )
    (net (code "38") (name "Net-(DA5-HO)") (class "Default")
      (node (ref "DA5") (pin "7") (pinfunction "HO_7") (pintype "passive"))
      (node (ref "R16") (pin "2") (pinfunction "2_2") (pintype "passive"))
      (node (ref "R18") (pin "2") (pinfunction "2_2") (pintype "passive"))
    )
    (net (code "39") (name "Net-(DA5-LO)") (class "Default")
      (node (ref "DA5") (pin "1") (pinfunction "LO_1") (pintype "passive"))
      (node (ref "R20") (pin "2") (pinfunction "2_2") (pintype "passive"))
      (node (ref "R24") (pin "2") (pinfunction "2_2") (pintype "passive"))
    )
    (net (code "40") (name "Net-(DA5-SD)") (class "Default")
      (node (ref "DA5") (pin "11") (pinfunction "SD_11") (pintype "passive"))
      (node (ref "R19") (pin "1") (pinfunction "1_1") (pintype "passive"))
    )
    (net (code "41") (name "Net-(DA5-VB)") (class "Default")
      (node (ref "C11") (pin "1") (pinfunction "1_1") (pintype "passive"))
      (node (ref "C12") (pin "2") (pinfunction "2_2") (pintype "passive"))
      (node (ref "C13") (pin "2") (pinfunction "2_2") (pintype "passive"))
      (node (ref "DA5") (pin "6") (pinfunction "VB_6") (pintype "passive"))
      (node (ref "VD6") (pin "C") (pinfunction "C_C") (pintype "passive"))
    )
    (net (code "42") (name "Net-(DA6-IN+)") (class "Default")
      (node (ref "C20") (pin "1") (pinfunction "1_1") (pintype "passive"))
      (node (ref "DA6") (pin "3") (pinfunction "IN+_3") (pintype "passive"))
      (node (ref "R21") (pin "1") (pinfunction "1_1") (pintype "passive"))
      (node (ref "R25") (pin "2") (pinfunction "2_2") (pintype "passive"))
    )
    (net (code "43") (name "Net-(DA6-IN-)") (class "Default")
      (node (ref "C20") (pin "2") (pinfunction "2_2") (pintype "passive"))
      (node (ref "C25") (pin "1") (pinfunction "1_1") (pintype "passive"))
      (node (ref "DA6") (pin "4") (pinfunction "IN-_4") (pintype "passive"))
      (node (ref "R28") (pin "2") (pinfunction "2_2") (pintype "passive"))
      (node (ref "R30") (pin "1") (pinfunction "1_1") (pintype "passive"))
    )
    (net (code "44") (name "Net-(DA6-OUT)") (class "Default")
      (node (ref "C25") (pin "2") (pinfunction "2_2") (pintype "passive"))
      (node (ref "DA6") (pin "1") (pinfunction "OUT_1") (pintype "passive"))
      (node (ref "R29") (pin "1") (pinfunction "1_1") (pintype "passive"))
      (node (ref "R30") (pin "2") (pinfunction "2_2") (pintype "passive"))
      (node (ref "R32") (pin "1") (pinfunction "1_1") (pintype "passive"))
    )
    (net (code "45") (name "Net-(DA7-+IN)") (class "Default")
      (node (ref "DA7") (pin "2") (pinfunction "+IN_2") (pintype "passive"))
      (node (ref "R23") (pin "2") (pinfunction "2_2") (pintype "passive"))
      (node (ref "R26") (pin "1") (pinfunction "1_1") (pintype "passive"))
    )
    (net (code "46") (name "Net-(DA7--IN)") (class "Default")
      (node (ref "DA7") (pin "3") (pinfunction "-IN_3") (pintype "passive"))
      (node (ref "R29") (pin "2") (pinfunction "2_2") (pintype "passive"))
    )
    (net (code "47") (name "Net-(DA8-HO)") (class "Default")
      (node (ref "DA8") (pin "7") (pinfunction "HO_7") (pintype "passive"))
      (node (ref "R33") (pin "2") (pinfunction "2_2") (pintype "passive"))
      (node (ref "R35") (pin "2") (pinfunction "2_2") (pintype "passive"))
    )
    (net (code "48") (name "Net-(DA8-LO)") (class "Default")
      (node (ref "DA8") (pin "1") (pinfunction "LO_1") (pintype "passive"))
      (node (ref "R37") (pin "2") (pinfunction "2_2") (pintype "passive"))
      (node (ref "R39") (pin "2") (pinfunction "2_2") (pintype "passive"))
    )
    (net (code "49") (name "Net-(DA8-SD)") (class "Default")
      (node (ref "DA8") (pin "11") (pinfunction "SD_11") (pintype "passive"))
      (node (ref "R36") (pin "1") (pinfunction "1_1") (pintype "passive"))
    )
    (net (code "50") (name "Net-(DA8-VB)") (class "Default")
      (node (ref "C21") (pin "1") (pinfunction "1_1") (pintype "passive"))
      (node (ref "C22") (pin "2") (pinfunction "2_2") (pintype "passive"))
      (node (ref "C24") (pin "2") (pinfunction "2_2") (pintype "passive"))
      (node (ref "DA8") (pin "6") (pinfunction "VB_6") (pintype "passive"))
      (node (ref "VD11") (pin "C") (pinfunction "C_C") (pintype "passive"))
    )
    (net (code "51") (name "Net-(R3-Pad1)") (class "Default")
      (node (ref "R3") (pin "1") (pinfunction "1_1") (pintype "passive"))
      (node (ref "VD1") (pin "A") (pinfunction "A_A") (pintype "passive"))
    )
    (net (code "52") (name "Net-(R4-Pad1)") (class "Default")
      (node (ref "R4") (pin "1") (pinfunction "1_1") (pintype "passive"))
      (node (ref "R5") (pin "1") (pinfunction "1_1") (pintype "passive"))
      (node (ref "VD2") (pin "C") (pinfunction "C_C") (pintype "passive"))
      (node (ref "VD3") (pin "A") (pinfunction "A_A") (pintype "passive"))
      (node (ref "VT1") (pin "G") (pinfunction "G_G") (pintype "passive"))
    )
    (net (code "53") (name "Net-(R6-Pad1)") (class "Default")
      (node (ref "R6") (pin "1") (pinfunction "1_1") (pintype "passive"))
      (node (ref "VD3") (pin "C") (pinfunction "C_C") (pintype "passive"))
    )
    (net (code "54") (name "Net-(R11-Pad1)") (class "Default")
      (node (ref "R11") (pin "1") (pinfunction "1_1") (pintype "passive"))
      (node (ref "R9") (pin "1") (pinfunction "1_1") (pintype "passive"))
      (node (ref "VD4") (pin "C") (pinfunction "C_C") (pintype "passive"))
      (node (ref "VD5") (pin "A") (pinfunction "A_A") (pintype "passive"))
    )
    (net (code "55") (name "Net-(R12-Pad1)") (class "Default")
      (node (ref "R12") (pin "1") (pinfunction "1_1") (pintype "passive"))
      (node (ref "VD5") (pin "C") (pinfunction "C_C") (pintype "passive"))
    )
    (net (code "56") (name "Net-(R14-Pad1)") (class "Default")
      (node (ref "R14") (pin "1") (pinfunction "1_1") (pintype "passive"))
      (node (ref "VD6") (pin "A") (pinfunction "A_A") (pintype "passive"))
    )
    (net (code "57") (name "Net-(R16-Pad1)") (class "Default")
      (node (ref "R16") (pin "1") (pinfunction "1_1") (pintype "passive"))
      (node (ref "R17") (pin "1") (pinfunction "1_1") (pintype "passive"))
      (node (ref "VD7") (pin "C") (pinfunction "C_C") (pintype "passive"))
      (node (ref "VD8") (pin "A") (pinfunction "A_A") (pintype "passive"))
      (node (ref "VT3") (pin "G") (pinfunction "G_G") (pintype "passive"))
    )
    (net (code "58") (name "Net-(R18-Pad1)") (class "Default")
      (node (ref "R18") (pin "1") (pinfunction "1_1") (pintype "passive"))
      (node (ref "VD8") (pin "C") (pinfunction "C_C") (pintype "passive"))
    )
    (net (code "59") (name "Net-(R20-Pad1)") (class "Default")
      (node (ref "R20") (pin "1") (pinfunction "1_1") (pintype "passive"))
      (node (ref "R22") (pin "1") (pinfunction "1_1") (pintype "passive"))
      (node (ref "VD10") (pin "A") (pinfunction "A_A") (pintype "passive"))
      (node (ref "VD9") (pin "C") (pinfunction "C_C") (pintype "passive"))
    )
    (net (code "60") (name "Net-(R24-Pad1)") (class "Default")
      (node (ref "R24") (pin "1") (pinfunction "1_1") (pintype "passive"))
      (node (ref "VD10") (pin "C") (pinfunction "C_C") (pintype "passive"))
    )
    (net (code "61") (name "Net-(R31-Pad1)") (class "Default")
      (node (ref "R31") (pin "1") (pinfunction "1_1") (pintype "passive"))
      (node (ref "VD11") (pin "A") (pinfunction "A_A") (pintype "passive"))
    )
    (net (code "62") (name "Net-(R33-Pad1)") (class "Default")
      (node (ref "R33") (pin "1") (pinfunction "1_1") (pintype "passive"))
      (node (ref "R34") (pin "1") (pinfunction "1_1") (pintype "passive"))
      (node (ref "VD12") (pin "C") (pinfunction "C_C") (pintype "passive"))
      (node (ref "VD13") (pin "A") (pinfunction "A_A") (pintype "passive"))
      (node (ref "VT5") (pin "G") (pinfunction "G_G") (pintype "passive"))
    )
    (net (code "63") (name "Net-(R35-Pad1)") (class "Default")
      (node (ref "R35") (pin "1") (pinfunction "1_1") (pintype "passive"))
      (node (ref "VD13") (pin "C") (pinfunction "C_C") (pintype "passive"))
    )
    (net (code "64") (name "Net-(R37-Pad1)") (class "Default")
      (node (ref "R37") (pin "1") (pinfunction "1_1") (pintype "passive"))
      (node (ref "R38") (pin "1") (pinfunction "1_1") (pintype "passive"))
      (node (ref "VD14") (pin "C") (pinfunction "C_C") (pintype "passive"))
      (node (ref "VD15") (pin "A") (pinfunction "A_A") (pintype "passive"))
    )
    (net (code "65") (name "Net-(R39-Pad1)") (class "Default")
      (node (ref "R39") (pin "1") (pinfunction "1_1") (pintype "passive"))
      (node (ref "VD15") (pin "C") (pinfunction "C_C") (pintype "passive"))
    )
    (net (code "66") (name "Power_GND") (class "Default")
      (node (ref "C17") (pin "1") (pinfunction "1_1") (pintype "passive"))
      (node (ref "C28") (pin "1") (pinfunction "1_1") (pintype "passive"))
      (node (ref "C7") (pin "1") (pinfunction "1_1") (pintype "passive"))
      (node (ref "R28") (pin "1") (pinfunction "1_1") (pintype "passive"))
      (node (ref "RS7") (pin "2") (pinfunction "2_2") (pintype "passive"))
      (node (ref "RS8") (pin "2") (pinfunction "2_2") (pintype "passive"))
    )
    (net (code "67") (name "unconnected-(VT2-PadG)") (class "Default")
      (node (ref "VT2") (pin "G") (pinfunction "G_G") (pintype "passive"))
    )
    (net (code "68") (name "unconnected-(VT4-PadG)") (class "Default")
      (node (ref "VT4") (pin "G") (pinfunction "G_G") (pintype "passive"))
    )
    (net (code "69") (name "unconnected-(VT6-PadG)") (class "Default")
      (node (ref "VT6") (pin "G") (pinfunction "G_G") (pintype "passive"))
    )
  )
)
